# subckt_analog_supplies.net
KiCad netlist of a schematic drawn in Altium Designer
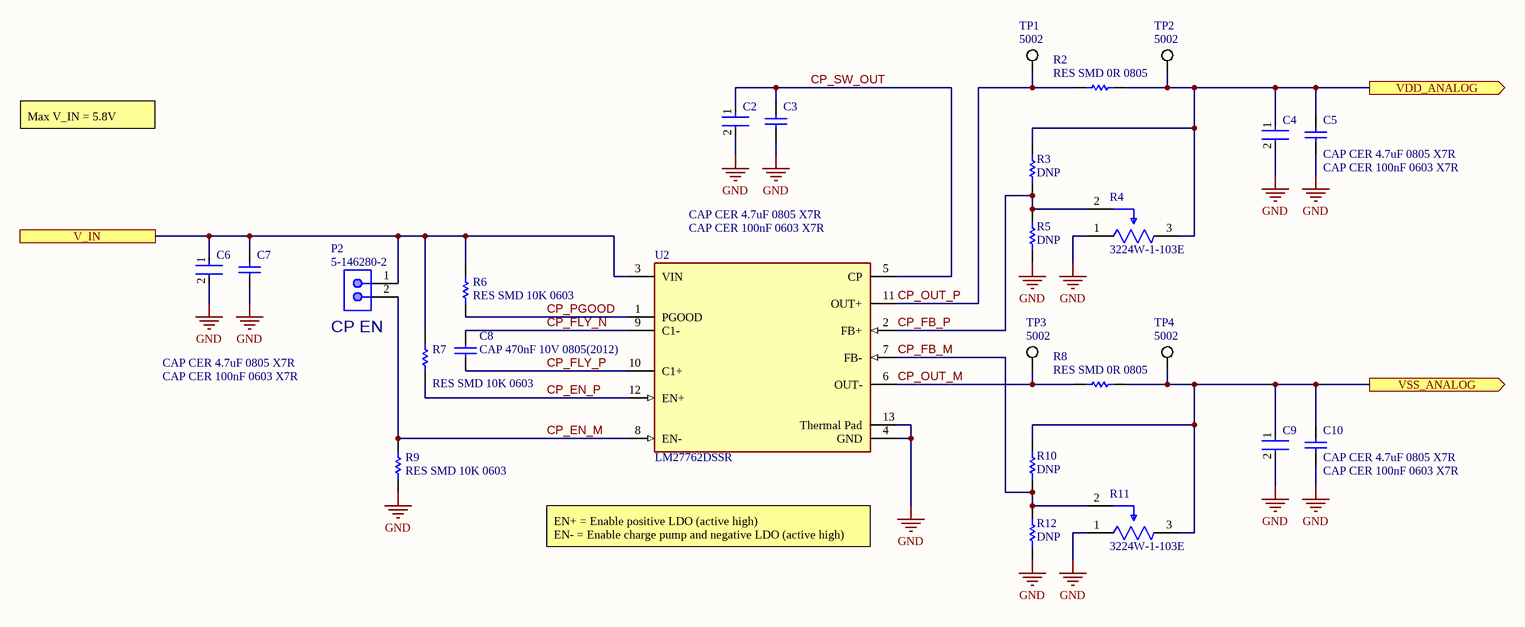
[diagram p0: subckt_analog_supplies.SchDoc]

(export (version "E")
  (design (tool "Eeschema 10.0.6"))
  (components
    (comp (ref "C2")
      (value "CAP CER 100nF 0603 X7R")
      (footprint "FP-CC0603-DA-MFG")
      (description "CAP CER 0.1UF 16V X7R 0603")
      (fields
        (field (name "OCTOPART") "https://octopart.com/cc0603krx7r7bb104-yageo-192941")
        (field (name "TOLERANCE") "0.1")
      )
      (libsource (lib "Altium Content Vault") (part "11868f565c42a9108669ba33697ecf6"))
    )
    (comp (ref "C3")
      (value "CAP CER 4.7uF 0805 X7R")
      (footprint "CAPC2013X140X50NL20T25")
      (fields
        (field (name "PART NUMBER") "0805ZC475KAT2A")
        (field (name "MANUFACTURER") "AVX Interconnect / Elco")
      )
      (libsource (lib "Altium Content Vault") (part "CAP"))
    )
    (comp (ref "C4")
      (value "CAP CER 100nF 0603 X7R")
      (footprint "FP-CC0603-DA-MFG")
      (description "CAP CER 0.1UF 16V X7R 0603")
      (fields
        (field (name "OCTOPART") "https://octopart.com/cc0603krx7r7bb104-yageo-192941")
        (field (name "TOLERANCE") "0.1")
      )
      (libsource (lib "Altium Content Vault") (part "11868f565c42a9108669ba33697ecf6"))
    )
    (comp (ref "C5")
      (value "CAP CER 4.7uF 0805 X7R")
      (footprint "CAPC2013X140X50NL20T25")
      (fields
        (field (name "PART NUMBER") "0805ZC475KAT2A")
        (field (name "MANUFACTURER") "AVX Interconnect / Elco")
      )
      (libsource (lib "Altium Content Vault") (part "CAP"))
    )
    (comp (ref "C6")
      (value "CAP CER 100nF 0603 X7R")
      (footprint "FP-CC0603-DA-MFG")
      (description "CAP CER 0.1UF 16V X7R 0603")
      (fields
        (field (name "OCTOPART") "https://octopart.com/cc0603krx7r7bb104-yageo-192941")
        (field (name "TOLERANCE") "0.1")
      )
      (libsource (lib "Altium Content Vault") (part "11868f565c42a9108669ba33697ecf6"))
    )
    (comp (ref "C7")
      (value "CAP CER 4.7uF 0805 X7R")
      (footprint "CAPC2013X140X50NL20T25")
      (fields
        (field (name "PART NUMBER") "0805ZC475KAT2A")
        (field (name "MANUFACTURER") "AVX Interconnect / Elco")
      )
      (libsource (lib "Altium Content Vault") (part "CAP"))
    )
    (comp (ref "C8")
      (value "CAP 470nF 10V 0805(2012)")
      (footprint "CAPC0805(2012)145_M")
      (description "CAP 470nF 10V ±5% 0805 (2012 Metric) Thickness 1.45mm SMD")
      (fields (field (name "TOLERANCE") "Â±5%"))
      (libsource (lib "Altium Content Vault") (part "CAP"))
    )
    (comp (ref "C9")
      (value "CAP CER 100nF 0603 X7R")
      (footprint "FP-CC0603-DA-MFG")
      (description "CAP CER 0.1UF 16V X7R 0603")
      (fields
        (field (name "OCTOPART") "https://octopart.com/cc0603krx7r7bb104-yageo-192941")
        (field (name "TOLERANCE") "0.1")
      )
      (libsource (lib "Altium Content Vault") (part "11868f565c42a9108669ba33697ecf6"))
    )
    (comp (ref "C10")
      (value "CAP CER 4.7uF 0805 X7R")
      (footprint "CAPC2013X140X50NL20T25")
      (fields
        (field (name "PART NUMBER") "0805ZC475KAT2A")
        (field (name "MANUFACTURER") "AVX Interconnect / Elco")
      )
      (libsource (lib "Altium Content Vault") (part "CAP"))
    )
    (comp (ref "P2")
      (value "5-146280-2")
      (footprint "TECO-5-146280-2_V")
      (fields (field (name "MANUFACTURER") "TE Connectivity"))
      (libsource (lib "Altium Content Vault") (part "CN-1P-M-R2"))
    )
    (comp (ref "R2")
      (value "RES SMD 0R 0805")
      (footprint "RESC2013X55X40NL15T20")
      (fields (field (name "MANUFACTURER") "Vishay Dale") (field (name "PART NUMBER") "TNPW0805100RBEEA"))
      (libsource (lib "Altium Content Vault") (part "RES"))
    )
    (comp (ref "R3")
      (value "DNP")
      (footprint "RESC1608X55X30LL10T20_A")
      (description "Chip Resistor, 0 Ohm, +/- 5%, 100 mW, -55 to 155 degC, 0603 (1608 Metric), RoHS, Tape and Reel")
      (fields (field (name "TOLERANCE") "Jumper") (field (name "MANUFACTURER") "Rohm"))
      (libsource (lib "Altium Content Vault") (part "RES-2"))
    )
    (comp (ref "R4")
      (value "3224W-1-103E")
      (footprint "FP-3224W-MFG")
      (description "TRIMMER 10K OHM 0.25W J LEAD TOP")
      (fields (field (name "TOLERANCE") "10%") (field (name "MANUFACTURER") "Bourns"))
      (libsource (lib "Altium Content Vault") (part "83d3d349ed884d1db45cec512f27eb6"))
    )
    (comp (ref "R5")
      (value "DNP")
      (footprint "RESC1608X55X30LL10T20_A")
      (description "Chip Resistor, 0 Ohm, +/- 5%, 100 mW, -55 to 155 degC, 0603 (1608 Metric), RoHS, Tape and Reel")
      (fields (field (name "TOLERANCE") "Jumper") (field (name "MANUFACTURER") "Rohm"))
      (libsource (lib "Altium Content Vault") (part "RES-2"))
    )
    (comp (ref "R6")
      (value "RES SMD 10K 0603")
      (footprint "RESC1609X55X30LL15T15")
      (description "Chip Resistor, 10 KOhm, +/- 1%, 0.1 W, -55 to 155 degC, 0603 (1608 Metric), RoHS, Tape and Reel")
      (fields (field (name "TOLERANCE") "1%") (field (name "MANUFACTURER") "Panasonic"))
      (libsource (lib "Altium Content Vault") (part "RES-2"))
    )
    (comp (ref "R7")
      (value "RES SMD 10K 0603")
      (footprint "RESC1609X55X30LL15T15")
      (description "Chip Resistor, 10 KOhm, +/- 1%, 0.1 W, -55 to 155 degC, 0603 (1608 Metric), RoHS, Tape and Reel")
      (fields (field (name "TOLERANCE") "1%") (field (name "MANUFACTURER") "Panasonic"))
      (libsource (lib "Altium Content Vault") (part "RES-2"))
    )
    (comp (ref "R8")
      (value "RES SMD 0R 0805")
      (footprint "RESC2013X55X40NL15T20")
      (fields (field (name "MANUFACTURER") "Vishay Dale") (field (name "PART NUMBER") "TNPW0805100RBEEA"))
      (libsource (lib "Altium Content Vault") (part "RES"))
    )
    (comp (ref "R9")
      (value "RES SMD 10K 0603")
      (footprint "RESC1609X55X30LL15T15")
      (description "Chip Resistor, 10 KOhm, +/- 1%, 0.1 W, -55 to 155 degC, 0603 (1608 Metric), RoHS, Tape and Reel")
      (fields (field (name "TOLERANCE") "1%") (field (name "MANUFACTURER") "Panasonic"))
      (libsource (lib "Altium Content Vault") (part "RES-2"))
    )
    (comp (ref "R10")
      (value "DNP")
      (footprint "RESC1608X55X30LL10T20_A")
      (description "Chip Resistor, 0 Ohm, +/- 5%, 100 mW, -55 to 155 degC, 0603 (1608 Metric), RoHS, Tape and Reel")
      (fields (field (name "TOLERANCE") "Jumper") (field (name "MANUFACTURER") "Rohm"))
      (libsource (lib "Altium Content Vault") (part "RES-2"))
    )
    (comp (ref "R11")
      (value "3224W-1-103E")
      (footprint "FP-3224W-MFG")
      (description "TRIMMER 10K OHM 0.25W J LEAD TOP")
      (fields (field (name "TOLERANCE") "10%") (field (name "MANUFACTURER") "Bourns"))
      (libsource (lib "Altium Content Vault") (part "83d3d349ed884d1db45cec512f27eb6"))
    )
    (comp (ref "R12")
      (value "DNP")
      (footprint "RESC1608X55X30LL10T20_A")
      (description "Chip Resistor, 0 Ohm, +/- 5%, 100 mW, -55 to 155 degC, 0603 (1608 Metric), RoHS, Tape and Reel")
      (fields (field (name "TOLERANCE") "Jumper") (field (name "MANUFACTURER") "Rohm"))
      (libsource (lib "Altium Content Vault") (part "RES-2"))
    )
    (comp (ref "TP1")
      (value "5002")
      (footprint "KSTN-5002")
      (description "Test Point, White, 1-Pin THD, RoHS, Bulk")
      (fields (field (name "MANUFACTURER") "KeystoneElectronics"))
      (libsource (lib "Altium Content Vault") (part "KSTN-TP-5002"))
    )
    (comp (ref "TP2")
      (value "5002")
      (footprint "KSTN-5002")
      (description "Test Point, White, 1-Pin THD, RoHS, Bulk")
      (fields (field (name "MANUFACTURER") "KeystoneElectronics"))
      (libsource (lib "Altium Content Vault") (part "KSTN-TP-5002"))
    )
    (comp (ref "TP3")
      (value "5002")
      (footprint "KSTN-5002")
      (description "Test Point, White, 1-Pin THD, RoHS, Bulk")
      (fields (field (name "MANUFACTURER") "KeystoneElectronics"))
      (libsource (lib "Altium Content Vault") (part "KSTN-TP-5002"))
    )
    (comp (ref "TP4")
      (value "5002")
      (footprint "KSTN-5002")
      (description "Test Point, White, 1-Pin THD, RoHS, Bulk")
      (fields (field (name "MANUFACTURER") "KeystoneElectronics"))
      (libsource (lib "Altium Content Vault") (part "KSTN-TP-5002"))
    )
    (comp (ref "U2")
      (value "LM27762DSSR")
      (footprint "FP-DSS0012B-MFG")
      (description "IC REG CHARGE PUMP ADJ DL 12WSON")
      (libsource (lib "Altium Content Vault") (part "ab275a4f98ccada617dcf409ec46a20"))
    )
  )
  (nets
    (net (code "1") (name "/CP_EN_M") (class "Default")
      (node (ref "P2") (pin "2") (pinfunction "2_2") (pintype "passive"))
      (node (ref "R9") (pin "2") (pinfunction "2_2") (pintype "passive"))
      (node (ref "U2") (pin "8") (pinfunction "EN-_8") (pintype "input"))
    )
    (net (code "2") (name "/CP_EN_P") (class "Default")
      (node (ref "R7") (pin "1") (pinfunction "1_1") (pintype "passive"))
      (node (ref "U2") (pin "12") (pinfunction "EN+_12") (pintype "input"))
    )
    (net (code "3") (name "/CP_FB_M") (class "Default")
      (node (ref "R10") (pin "1") (pinfunction "1_1") (pintype "passive"))
      (node (ref "R11") (pin "2") (pinfunction "WIPER_2") (pintype "passive"))
      (node (ref "R12") (pin "2") (pinfunction "2_2") (pintype "passive"))
      (node (ref "U2") (pin "7") (pinfunction "FB-_7") (pintype "input"))
    )
    (net (code "4") (name "/CP_FB_P") (class "Default")
      (node (ref "R3") (pin "1") (pinfunction "1_1") (pintype "passive"))
      (node (ref "R4") (pin "2") (pinfunction "WIPER_2") (pintype "passive"))
      (node (ref "R5") (pin "2") (pinfunction "2_2") (pintype "passive"))
      (node (ref "U2") (pin "2") (pinfunction "FB+_2") (pintype "input"))
    )
    (net (code "5") (name "/CP_FLY_N") (class "Default")
      (node (ref "C8") (pin "2") (pinfunction "2_2") (pintype "passive"))
      (node (ref "U2") (pin "9") (pinfunction "C1-_9") (pintype "passive"))
    )
    (net (code "6") (name "/CP_FLY_P") (class "Default")
      (node (ref "C8") (pin "1") (pinfunction "1_1") (pintype "passive"))
      (node (ref "U2") (pin "10") (pinfunction "C1+_10") (pintype "passive"))
    )
    (net (code "7") (name "/CP_OUT_M") (class "Default")
      (node (ref "R8") (pin "1") (pinfunction "1_1") (pintype "passive"))
      (node (ref "TP3") (pin "1") (pintype "passive"))
      (node (ref "U2") (pin "6") (pinfunction "OUT-_6") (pintype "passive"))
    )
    (net (code "8") (name "/CP_OUT_P") (class "Default")
      (node (ref "R2") (pin "1") (pinfunction "1_1") (pintype "passive"))
      (node (ref "TP1") (pin "1") (pintype "passive"))
      (node (ref "U2") (pin "11") (pinfunction "OUT+_11") (pintype "passive"))
    )
    (net (code "9") (name "/CP_PGOOD") (class "Default")
      (node (ref "R6") (pin "1") (pinfunction "1_1") (pintype "passive"))
      (node (ref "U2") (pin "1") (pinfunction "PGOOD_1") (pintype "open_collector"))
    )
    (net (code "10") (name "/CP_SW_OUT") (class "Default")
      (node (ref "C2") (pin "1") (pinfunction "1_1") (pintype "passive"))
      (node (ref "C3") (pin "1") (pinfunction "1_1") (pintype "passive"))
      (node (ref "U2") (pin "5") (pinfunction "CP_5") (pintype "passive"))
    )
    (net (code "11") (name "/VDD_ANALOG") (class "Default")
      (node (ref "C4") (pin "1") (pinfunction "1_1") (pintype "passive"))
      (node (ref "C5") (pin "1") (pinfunction "1_1") (pintype "passive"))
      (node (ref "R2") (pin "2") (pinfunction "2_2") (pintype "passive"))
      (node (ref "R3") (pin "2") (pinfunction "2_2") (pintype "passive"))
      (node (ref "R4") (pin "3") (pinfunction "CW_3") (pintype "passive"))
      (node (ref "TP2") (pin "1") (pintype "passive"))
    )
    (net (code "12") (name "/VSS_ANALOG") (class "Default")
      (node (ref "C10") (pin "1") (pinfunction "1_1") (pintype "passive"))
      (node (ref "C9") (pin "1") (pinfunction "1_1") (pintype "passive"))
      (node (ref "R10") (pin "2") (pinfunction "2_2") (pintype "passive"))
      (node (ref "R11") (pin "3") (pinfunction "CW_3") (pintype "passive"))
      (node (ref "R8") (pin "2") (pinfunction "2_2") (pintype "passive"))
      (node (ref "TP4") (pin "1") (pintype "passive"))
    )
    (net (code "13") (name "/V_IN") (class "Default")
      (node (ref "C6") (pin "1") (pinfunction "1_1") (pintype "passive"))
      (node (ref "C7") (pin "1") (pinfunction "1_1") (pintype "passive"))
      (node (ref "P2") (pin "1") (pinfunction "1_1") (pintype "passive"))
      (node (ref "R6") (pin "2") (pinfunction "2_2") (pintype "passive"))
      (node (ref "R7") (pin "2") (pinfunction "2_2") (pintype "passive"))
      (node (ref "U2") (pin "3") (pinfunction "VIN_3") (pintype "power_in"))
    )
    (net (code "14") (name "GND") (class "Default")
      (node (ref "C10") (pin "2") (pinfunction "2_2") (pintype "passive"))
      (node (ref "C2") (pin "2") (pinfunction "2_2") (pintype "passive"))
      (node (ref "C3") (pin "2") (pinfunction "2_2") (pintype "passive"))
      (node (ref "C4") (pin "2") (pinfunction "2_2") (pintype "passive"))
      (node (ref "C5") (pin "2") (pinfunction "2_2") (pintype "passive"))
      (node (ref "C6") (pin "2") (pinfunction "2_2") (pintype "passive"))
      (node (ref "C7") (pin "2") (pinfunction "2_2") (pintype "passive"))
      (node (ref "C9") (pin "2") (pinfunction "2_2") (pintype "passive"))
      (node (ref "R11") (pin "1") (pinfunction "CCW_1") (pintype "passive"))
      (node (ref "R12") (pin "1") (pinfunction "1_1") (pintype "passive"))
      (node (ref "R4") (pin "1") (pinfunction "CCW_1") (pintype "passive"))
      (node (ref "R5") (pin "1") (pinfunction "1_1") (pintype "passive"))
      (node (ref "R9") (pin "1") (pinfunction "1_1") (pintype "passive"))
      (node (ref "U2") (pin "13") (pinfunction "Thermal_Pad_13") (pintype "passive"))
      (node (ref "U2") (pin "4") (pinfunction "GND_4") (pintype "power_in"))
    )
  )
)
